# AmbaSat-1-SolarBoard.net
KiCad netlist of a schematic drawn in EAGLE
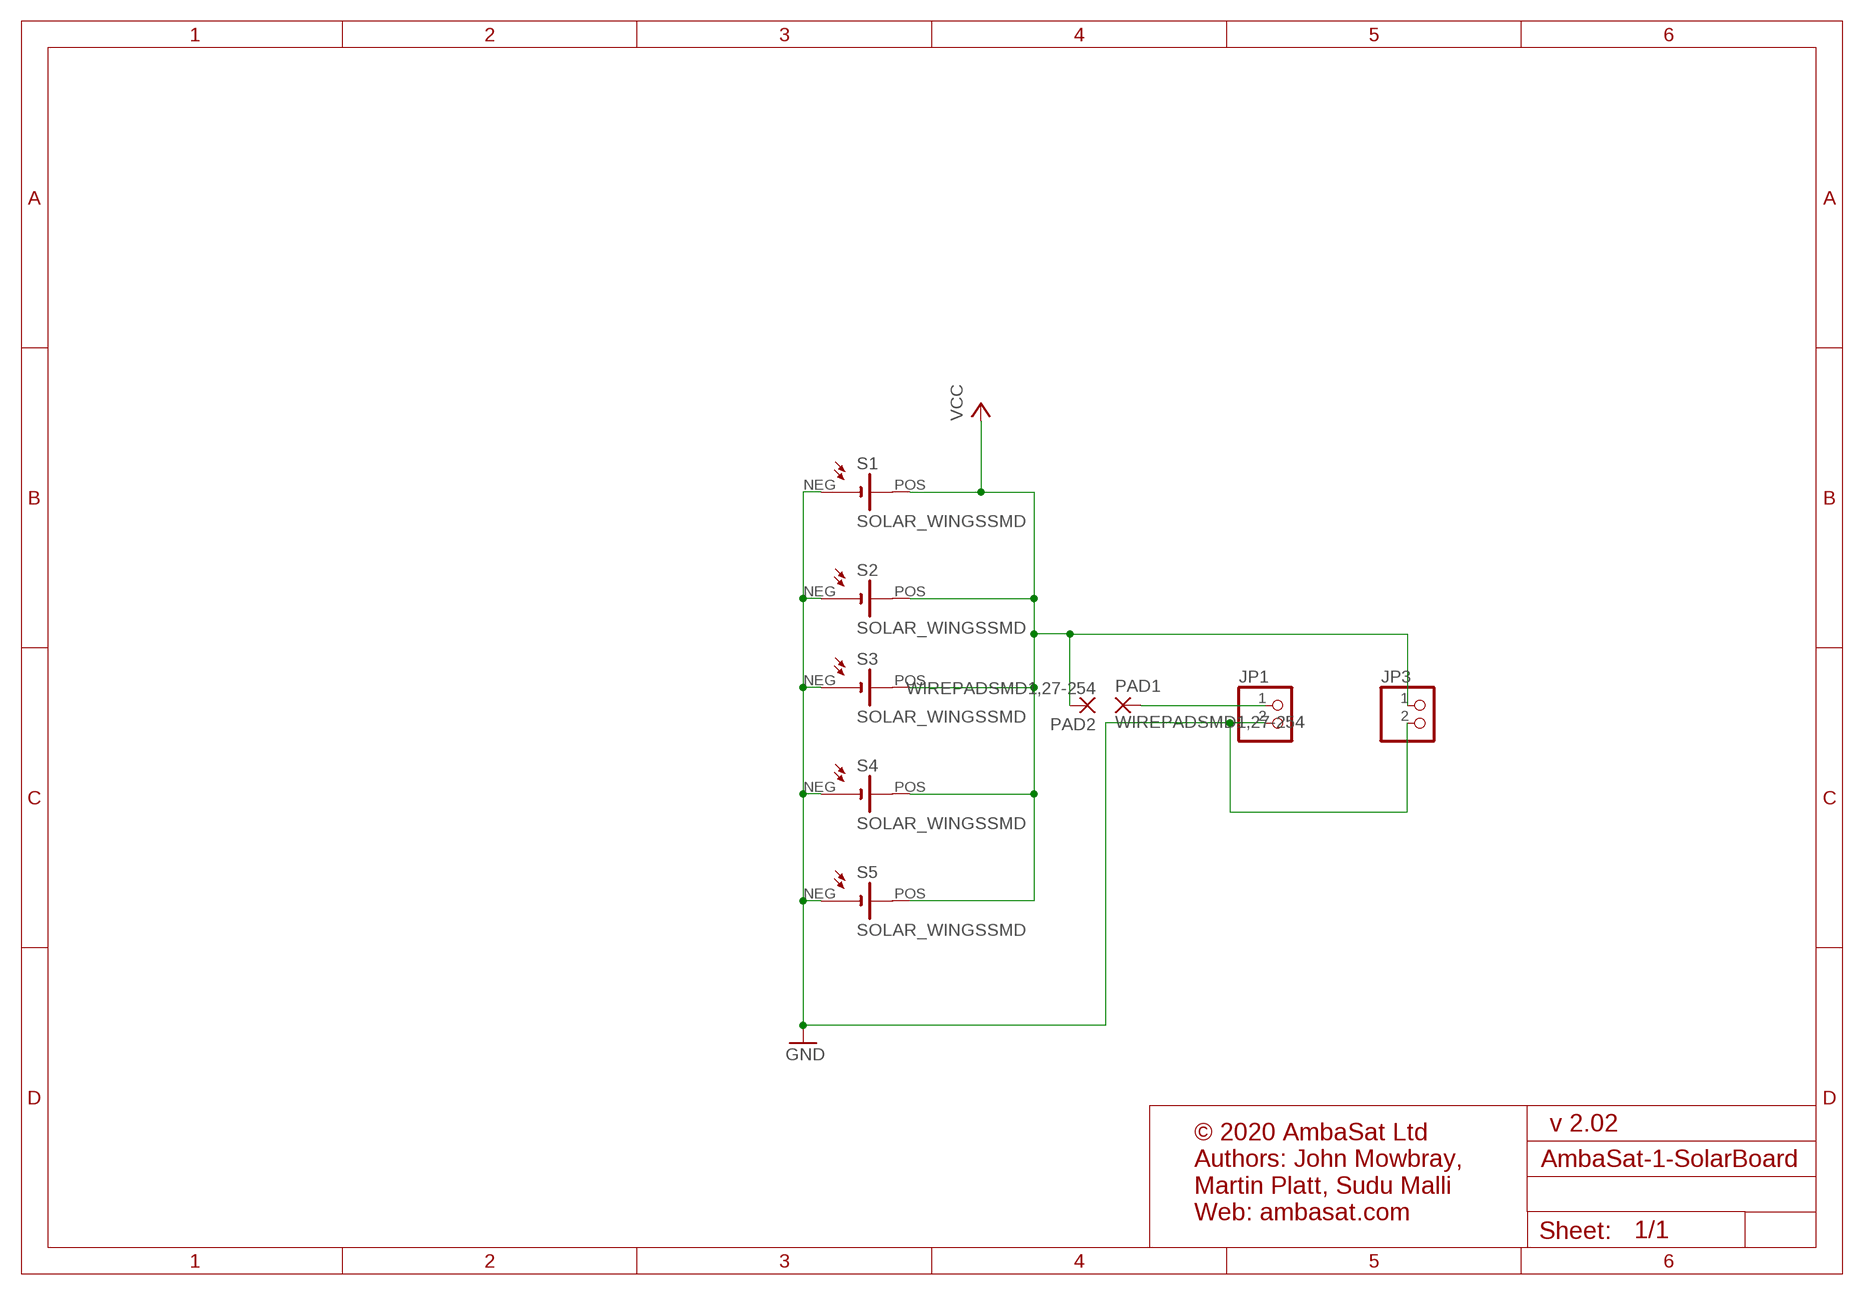
[diagram p0: schematic, sheet 1]

(export (version "E")
  (design (tool "Eeschema 10.0.6"))
  (components
    (comp (ref "JP1")
      (value "PINHD-1X2")
      (footprint "eagle-import:1X02")
      (libsource (lib "eagle-import") (part "PINHD-1X2"))
    )
    (comp (ref "JP3")
      (value "PINHD-1X2")
      (footprint "eagle-import:1X02")
      (libsource (lib "eagle-import") (part "pinhead_325_PINHD-1X2"))
    )
    (comp (ref "PAD1")
      (value "WIREPADSMD1,27-254")
      (footprint "eagle-import:SMD1,27-2,54")
      (libsource (lib "eagle-import") (part "WIREPADSMD1,27-254"))
    )
    (comp (ref "PAD2")
      (value "WIREPADSMD1,27-254")
      (footprint "eagle-import:SMD1,27-2,54")
      (libsource (lib "eagle-import") (part "WIREPADSMD1,27-254"))
    )
    (comp (ref "S1")
      (value "SOLAR_WINGSSMD")
      (footprint "eagle-import:SOLAR_WINGS_SMD")
      (libsource (lib "eagle-import") (part "SOLAR_WINGSSMD"))
    )
    (comp (ref "S2")
      (value "SOLAR_WINGSSMD")
      (footprint "eagle-import:SOLAR_WINGS_SMD")
      (libsource (lib "eagle-import") (part "SOLAR_WINGSSMD"))
    )
    (comp (ref "S3")
      (value "SOLAR_WINGSSMD")
      (footprint "eagle-import:SOLAR_WINGS_SMD")
      (libsource (lib "eagle-import") (part "SOLAR_WINGSSMD"))
    )
    (comp (ref "S4")
      (value "SOLAR_WINGSSMD")
      (footprint "eagle-import:SOLAR_WINGS_SMD")
      (libsource (lib "eagle-import") (part "SOLAR_WINGSSMD"))
    )
    (comp (ref "S5")
      (value "SOLAR_WINGSSMD")
      (footprint "eagle-import:SOLAR_WINGS_SMD")
      (libsource (lib "eagle-import") (part "SOLAR_WINGSSMD"))
    )
  )
  (nets
    (net (code "1") (name "GND") (class "Default")
      (node (ref "JP1") (pin "2") (pinfunction "2_2") (pintype "passive"))
      (node (ref "JP3") (pin "2") (pinfunction "2_2") (pintype "passive"))
      (node (ref "S1") (pin "NEG") (pinfunction "NEG_NEG") (pintype "bidirectional"))
      (node (ref "S2") (pin "NEG") (pinfunction "NEG_NEG") (pintype "bidirectional"))
      (node (ref "S3") (pin "NEG") (pinfunction "NEG_NEG") (pintype "bidirectional"))
      (node (ref "S4") (pin "NEG") (pinfunction "NEG_NEG") (pintype "bidirectional"))
      (node (ref "S5") (pin "NEG") (pinfunction "NEG_NEG") (pintype "bidirectional"))
    )
    (net (code "2") (name "Net-(PAD1-P)") (class "Default")
      (node (ref "JP1") (pin "1") (pinfunction "1_1") (pintype "passive"))
      (node (ref "PAD1") (pin "1") (pinfunction "P_1") (pintype "passive"))
    )
    (net (code "3") (name "VCC") (class "Default")
      (node (ref "JP3") (pin "1") (pinfunction "1_1") (pintype "passive"))
      (node (ref "PAD2") (pin "1") (pinfunction "P_1") (pintype "passive"))
      (node (ref "S1") (pin "POS") (pinfunction "POS_POS") (pintype "bidirectional"))
      (node (ref "S2") (pin "POS") (pinfunction "POS_POS") (pintype "bidirectional"))
      (node (ref "S3") (pin "POS") (pinfunction "POS_POS") (pintype "bidirectional"))
      (node (ref "S4") (pin "POS") (pinfunction "POS_POS") (pintype "bidirectional"))
      (node (ref "S5") (pin "POS") (pinfunction "POS_POS") (pintype "bidirectional"))
    )
  )
)
